# power-distribution_soccer-robot-2.net
KiCad netlist of a schematic drawn in EAGLE
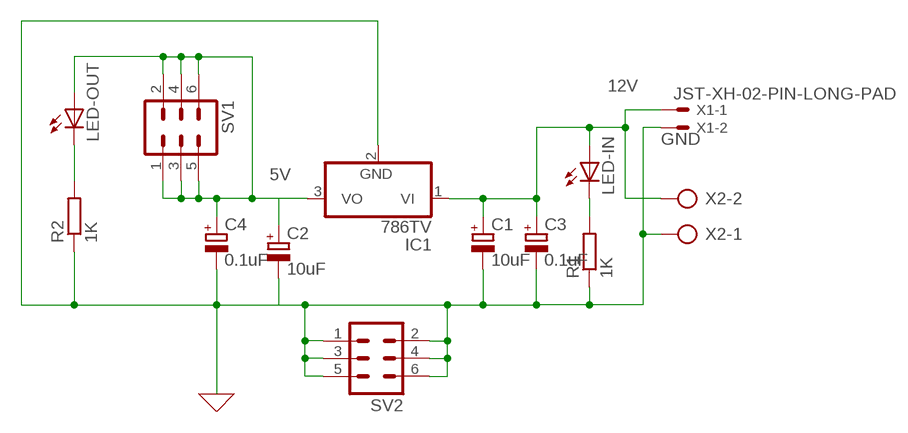
[diagram p0: schematic, sheet 1]

(export (version "E")
  (design (tool "Eeschema 10.0.6"))
  (components
    (comp (ref "C1")
      (value "10uF")
      (footprint "eagle-import:E2,5-6E")
      (libsource (lib "eagle-import") (part "CPOL-EUE2,5-6E"))
    )
    (comp (ref "C2")
      (value "10uF")
      (footprint "eagle-import:E2,5-6E")
      (libsource (lib "eagle-import") (part "CPOL-EUE2,5-6E"))
    )
    (comp (ref "C3")
      (value "0.1uF")
      (footprint "eagle-import:E2,5-6E")
      (libsource (lib "eagle-import") (part "CPOL-EUE2,5-6E"))
    )
    (comp (ref "C4")
      (value "0.1uF")
      (footprint "eagle-import:E2,5-6E")
      (libsource (lib "eagle-import") (part "CPOL-EUE2,5-6E"))
    )
    (comp (ref "IC1")
      (value "786TV")
      (footprint "eagle-import:TO220V")
      (libsource (lib "eagle-import") (part "78TV6"))
    )
    (comp (ref "LED-IN")
      (value "LED5MM")
      (footprint "eagle-import:LED5MM")
      (libsource (lib "eagle-import") (part "LED5MM"))
    )
    (comp (ref "LED-OUT")
      (value "LED5MM")
      (footprint "eagle-import:LED5MM")
      (libsource (lib "eagle-import") (part "LED5MM"))
    )
    (comp (ref "R1")
      (value "1K")
      (footprint "eagle-import:0204_5")
      (libsource (lib "eagle-import") (part "R-EU_0204/5"))
    )
    (comp (ref "R2")
      (value "1K")
      (footprint "eagle-import:0204_5")
      (libsource (lib "eagle-import") (part "R-EU_0204/5"))
    )
    (comp (ref "SV1")
      (value "MA03-2")
      (footprint "eagle-import:MA03-2(2)")
      (libsource (lib "eagle-import") (part "MA03-2"))
    )
    (comp (ref "SV2")
      (value "MA03-2")
      (footprint "eagle-import:MA03-2(2)")
      (libsource (lib "eagle-import") (part "MA03-2"))
    )
    (comp (ref "X1")
      (value "JST-XH-02-PIN-LONG-PAD")
      (footprint "eagle-import:JST-XH-02-PACKAGE-LONG-PAD")
      (libsource (lib "eagle-import") (part "JST-XH-02-PIN-LONG-PAD"))
    )
    (comp (ref "X2")
      (value "AK500/2-H")
      (footprint "eagle-import:AK500_2-H")
      (libsource (lib "eagle-import") (part "AK500/2-H"))
    )
  )
  (nets
    (net (code "1") (name "/5V") (class "Default")
      (node (ref "C2") (pin "+") (pinfunction "+_+") (pintype "passive"))
      (node (ref "C4") (pin "+") (pinfunction "+_+") (pintype "passive"))
      (node (ref "IC1") (pin "3") (pinfunction "VO_3") (pintype "passive"))
      (node (ref "LED-OUT") (pin "A") (pinfunction "A_A") (pintype "passive"))
      (node (ref "SV1") (pin "1") (pinfunction "1_1") (pintype "passive"))
      (node (ref "SV1") (pin "2") (pinfunction "2_2") (pintype "passive"))
      (node (ref "SV1") (pin "3") (pinfunction "3_3") (pintype "passive"))
      (node (ref "SV1") (pin "4") (pinfunction "4_4") (pintype "passive"))
      (node (ref "SV1") (pin "5") (pinfunction "5_5") (pintype "passive"))
      (node (ref "SV1") (pin "6") (pinfunction "6_6") (pintype "passive"))
    )
    (net (code "2") (name "/12V") (class "Default")
      (node (ref "C1") (pin "+") (pinfunction "+_+") (pintype "passive"))
      (node (ref "C3") (pin "+") (pinfunction "+_+") (pintype "passive"))
      (node (ref "IC1") (pin "1") (pinfunction "VI_1") (pintype "input"))
      (node (ref "LED-IN") (pin "A") (pinfunction "A_A") (pintype "passive"))
      (node (ref "X1") (pin "1") (pinfunction "S_1") (pintype "passive"))
      (node (ref "X2") (pin "2") (pinfunction "KL_2") (pintype "passive"))
    )
    (net (code "3") (name "GND") (class "Default")
      (node (ref "C1") (pin "-") (pinfunction "-_-") (pintype "passive"))
      (node (ref "C2") (pin "-") (pinfunction "-_-") (pintype "passive"))
      (node (ref "C3") (pin "-") (pinfunction "-_-") (pintype "passive"))
      (node (ref "C4") (pin "-") (pinfunction "-_-") (pintype "passive"))
      (node (ref "IC1") (pin "2") (pinfunction "GND_2") (pintype "passive"))
      (node (ref "R1") (pin "1") (pinfunction "1_1") (pintype "passive"))
      (node (ref "R2") (pin "1") (pinfunction "1_1") (pintype "passive"))
      (node (ref "SV2") (pin "1") (pinfunction "1_1") (pintype "passive"))
      (node (ref "SV2") (pin "2") (pinfunction "2_2") (pintype "passive"))
      (node (ref "SV2") (pin "3") (pinfunction "3_3") (pintype "passive"))
      (node (ref "SV2") (pin "4") (pinfunction "4_4") (pintype "passive"))
      (node (ref "SV2") (pin "5") (pinfunction "5_5") (pintype "passive"))
      (node (ref "SV2") (pin "6") (pinfunction "6_6") (pintype "passive"))
      (node (ref "X1") (pin "2") (pinfunction "S_2") (pintype "passive"))
      (node (ref "X2") (pin "1") (pinfunction "KL_1") (pintype "passive"))
    )
    (net (code "4") (name "Net-(LED-IN-C)") (class "Default")
      (node (ref "LED-IN") (pin "K") (pinfunction "C_K") (pintype "passive"))
      (node (ref "R1") (pin "2") (pinfunction "2_2") (pintype "passive"))
    )
    (net (code "5") (name "Net-(LED-OUT-C)") (class "Default")
      (node (ref "LED-OUT") (pin "K") (pinfunction "C_K") (pintype "passive"))
      (node (ref "R2") (pin "2") (pinfunction "2_2") (pintype "passive"))
    )
  )
)
